# HDMI_Extension_Schematics.net
KiCad netlist of a schematic drawn in Altium Designer
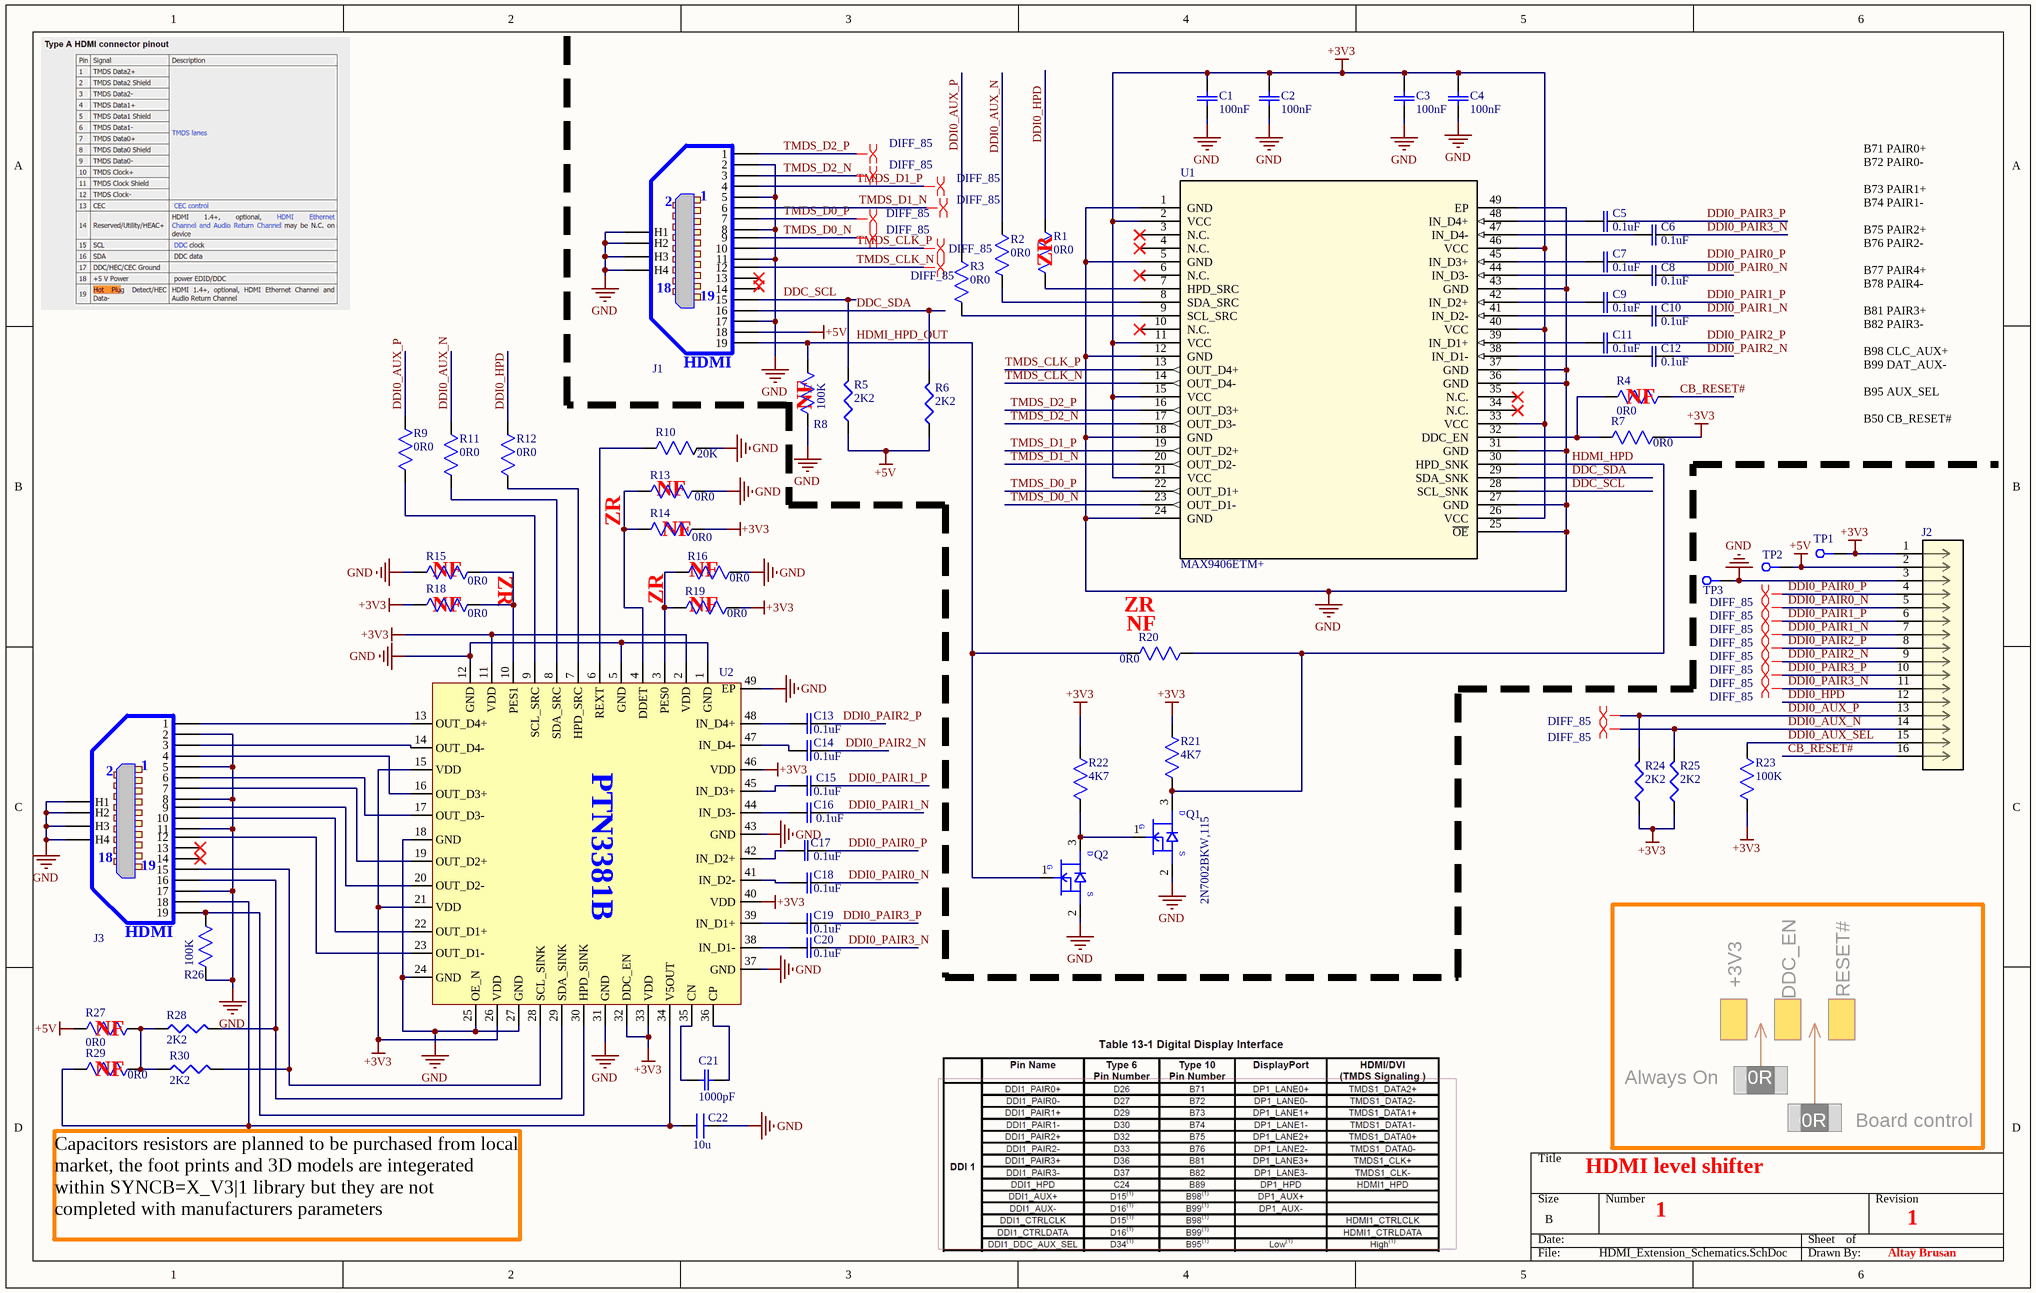
[diagram p0: HDMI_Extension_Schematics.SchDoc]

(export (version "E")
  (design (tool "Eeschema 10.0.6"))
  (components
    (comp (ref "C1")
      (value "100nF")
      (footprint "STA_RMCF1206-M")
      (description "CAP CER 0.1UF 50V X8R 0603")
      (fields (field (name "TOLERANCE") "±10%"))
      (libsource (lib "SYNCBOX_V3I1") (part "CL05A104KA5NNNC"))
    )
    (comp (ref "C2")
      (value "100nF")
      (footprint "STA_RMCF1206-M")
      (description "CAP CER 0.1UF 50V X8R 0603")
      (fields (field (name "TOLERANCE") "±10%"))
      (libsource (lib "SYNCBOX_V3I1") (part "CL05A104KA5NNNC"))
    )
    (comp (ref "C3")
      (value "100nF")
      (footprint "STA_RMCF1206-M")
      (description "CAP CER 0.1UF 50V X8R 0603")
      (fields (field (name "TOLERANCE") "±10%"))
      (libsource (lib "SYNCBOX_V3I1") (part "CL05A104KA5NNNC"))
    )
    (comp (ref "C4")
      (value "100nF")
      (footprint "STA_RMCF1206-M")
      (description "CAP CER 0.1UF 50V X8R 0603")
      (fields (field (name "TOLERANCE") "±10%"))
      (libsource (lib "SYNCBOX_V3I1") (part "CL05A104KA5NNNC"))
    )
    (comp (ref "C5")
      (value "0.1uF")
      (footprint "CAP_3216")
      (description "CAP CER 0.1UF 100V X8R 1206")
      (fields
        (field (name "MANUFACTURER_PART_NUMBER") "C3216X8R2A104K115AA")
        (field (name "COPYRIGHT") "Copyright (C) 2018 Accelerated Designs. All rights reserved")
      )
      (libsource (lib "SYNCBOX_V3I1") (part "C3216X8R2A104K11"))
    )
    (comp (ref "C6")
      (value "0.1uF")
      (footprint "CAP_3216")
      (description "CAP CER 0.1UF 100V X8R 1206")
      (fields
        (field (name "MANUFACTURER_PART_NUMBER") "C3216X8R2A104K115AA")
        (field (name "COPYRIGHT") "Copyright (C) 2018 Accelerated Designs. All rights reserved")
      )
      (libsource (lib "SYNCBOX_V3I1") (part "C3216X8R2A104K11"))
    )
    (comp (ref "C7")
      (value "0.1uF")
      (footprint "CAP_3216")
      (description "CAP CER 0.1UF 100V X8R 1206")
      (fields
        (field (name "MANUFACTURER_PART_NUMBER") "C3216X8R2A104K115AA")
        (field (name "COPYRIGHT") "Copyright (C) 2018 Accelerated Designs. All rights reserved")
      )
      (libsource (lib "SYNCBOX_V3I1") (part "C3216X8R2A104K11"))
    )
    (comp (ref "C8")
      (value "0.1uF")
      (footprint "CAP_3216")
      (description "CAP CER 0.1UF 100V X8R 1206")
      (fields
        (field (name "MANUFACTURER_PART_NUMBER") "C3216X8R2A104K115AA")
        (field (name "COPYRIGHT") "Copyright (C) 2018 Accelerated Designs. All rights reserved")
      )
      (libsource (lib "SYNCBOX_V3I1") (part "C3216X8R2A104K11"))
    )
    (comp (ref "C9")
      (value "0.1uF")
      (footprint "CAP_3216")
      (description "CAP CER 0.1UF 100V X8R 1206")
      (fields
        (field (name "MANUFACTURER_PART_NUMBER") "C3216X8R2A104K115AA")
        (field (name "COPYRIGHT") "Copyright (C) 2018 Accelerated Designs. All rights reserved")
      )
      (libsource (lib "SYNCBOX_V3I1") (part "C3216X8R2A104K11"))
    )
    (comp (ref "C10")
      (value "0.1uF")
      (footprint "CAP_3216")
      (description "CAP CER 0.1UF 100V X8R 1206")
      (fields
        (field (name "MANUFACTURER_PART_NUMBER") "C3216X8R2A104K115AA")
        (field (name "COPYRIGHT") "Copyright (C) 2018 Accelerated Designs. All rights reserved")
      )
      (libsource (lib "SYNCBOX_V3I1") (part "C3216X8R2A104K11"))
    )
    (comp (ref "C11")
      (value "0.1uF")
      (footprint "CAP_3216")
      (description "CAP CER 0.1UF 100V X8R 1206")
      (fields
        (field (name "MANUFACTURER_PART_NUMBER") "C3216X8R2A104K115AA")
        (field (name "COPYRIGHT") "Copyright (C) 2018 Accelerated Designs. All rights reserved")
      )
      (libsource (lib "SYNCBOX_V3I1") (part "C3216X8R2A104K11"))
    )
    (comp (ref "C12")
      (value "0.1uF")
      (footprint "CAP_3216")
      (description "CAP CER 0.1UF 100V X8R 1206")
      (fields
        (field (name "MANUFACTURER_PART_NUMBER") "C3216X8R2A104K115AA")
        (field (name "COPYRIGHT") "Copyright (C) 2018 Accelerated Designs. All rights reserved")
      )
      (libsource (lib "SYNCBOX_V3I1") (part "C3216X8R2A104K11"))
    )
    (comp (ref "C13")
      (value "0.1uF")
      (footprint "CAP_3216")
      (description "CAP CER 0.1UF 100V X8R 1206")
      (fields
        (field (name "MANUFACTURER_PART_NUMBER") "C3216X8R2A104K115AA")
        (field (name "COPYRIGHT") "Copyright (C) 2018 Accelerated Designs. All rights reserved")
      )
      (libsource (lib "SYNCBOX_V3I1") (part "C3216X8R2A104K11"))
    )
    (comp (ref "C14")
      (value "0.1uF")
      (footprint "CAP_3216")
      (description "CAP CER 0.1UF 100V X8R 1206")
      (fields
        (field (name "MANUFACTURER_PART_NUMBER") "C3216X8R2A104K115AA")
        (field (name "COPYRIGHT") "Copyright (C) 2018 Accelerated Designs. All rights reserved")
      )
      (libsource (lib "SYNCBOX_V3I1") (part "C3216X8R2A104K11"))
    )
    (comp (ref "C15")
      (value "0.1uF")
      (footprint "CAP_3216")
      (description "CAP CER 0.1UF 100V X8R 1206")
      (fields
        (field (name "MANUFACTURER_PART_NUMBER") "C3216X8R2A104K115AA")
        (field (name "COPYRIGHT") "Copyright (C) 2018 Accelerated Designs. All rights reserved")
      )
      (libsource (lib "SYNCBOX_V3I1") (part "C3216X8R2A104K11"))
    )
    (comp (ref "C16")
      (value "0.1uF")
      (footprint "CAP_3216")
      (description "CAP CER 0.1UF 100V X8R 1206")
      (fields
        (field (name "MANUFACTURER_PART_NUMBER") "C3216X8R2A104K115AA")
        (field (name "COPYRIGHT") "Copyright (C) 2018 Accelerated Designs. All rights reserved")
      )
      (libsource (lib "SYNCBOX_V3I1") (part "C3216X8R2A104K11"))
    )
    (comp (ref "C17")
      (value "0.1uF")
      (footprint "CAP_3216")
      (description "CAP CER 0.1UF 100V X8R 1206")
      (fields
        (field (name "MANUFACTURER_PART_NUMBER") "C3216X8R2A104K115AA")
        (field (name "COPYRIGHT") "Copyright (C) 2018 Accelerated Designs. All rights reserved")
      )
      (libsource (lib "SYNCBOX_V3I1") (part "C3216X8R2A104K11"))
    )
    (comp (ref "C18")
      (value "0.1uF")
      (footprint "CAP_3216")
      (description "CAP CER 0.1UF 100V X8R 1206")
      (fields
        (field (name "MANUFACTURER_PART_NUMBER") "C3216X8R2A104K115AA")
        (field (name "COPYRIGHT") "Copyright (C) 2018 Accelerated Designs. All rights reserved")
      )
      (libsource (lib "SYNCBOX_V3I1") (part "C3216X8R2A104K11"))
    )
    (comp (ref "C19")
      (value "0.1uF")
      (footprint "CAP_3216")
      (description "CAP CER 0.1UF 100V X8R 1206")
      (fields
        (field (name "MANUFACTURER_PART_NUMBER") "C3216X8R2A104K115AA")
        (field (name "COPYRIGHT") "Copyright (C) 2018 Accelerated Designs. All rights reserved")
      )
      (libsource (lib "SYNCBOX_V3I1") (part "C3216X8R2A104K11"))
    )
    (comp (ref "C20")
      (value "0.1uF")
      (footprint "CAP_3216")
      (description "CAP CER 0.1UF 100V X8R 1206")
      (fields
        (field (name "MANUFACTURER_PART_NUMBER") "C3216X8R2A104K115AA")
        (field (name "COPYRIGHT") "Copyright (C) 2018 Accelerated Designs. All rights reserved")
      )
      (libsource (lib "SYNCBOX_V3I1") (part "C3216X8R2A104K11"))
    )
    (comp (ref "C21")
      (value "1000pF")
      (footprint "C1206")
      (description "CAP CER 1206 1NF 2000V X7R 10% F")
      (fields (field (name "TOLERANCE") "±10%"))
      (libsource (lib "SYNCBOX_V3I1") (part "C1206X102KGRACAUTO"))
    )
    (comp (ref "C22")
      (value "10u")
      (footprint "C1206")
      (description "CAP CER 10UF 6.3V X5R 20% 0603")
      (fields (field (name "MANUFACTURER PART NUMBER") "C1608X5R0J106M") (field (name "TOLERANCE") "±20%"))
      (libsource (lib "SYNCBOX_V3I1") (part "C1608X5R0J106M"))
    )
    (comp (ref "J1")
      (value "HDMI Connector")
      (footprint "HDMI_Thru")
      (libsource (lib "SYNCBOX_V3I1") (part "HDMI_Connector"))
    )
    (comp (ref "J2")
      (value "Part Number: FTS-108-01-F-D")
      (footprint "CON16_2x8_TU_FTS")
      (description "No Description Available")
      (fields
        (field (name "MANUFACTURER_PART_NUMBER") "FTS-108-01-F-D")
        (field (name "COPYRIGHT") "Copyright (C) 2018 Accelerated Designs. All rights reserved")
      )
      (libsource (lib "SYNCBOX_V3I1") (part "FTS-108-01-F-D"))
    )
    (comp (ref "J3")
      (value "HDMI Connector")
      (footprint "HDMI_Thru")
      (libsource (lib "SYNCBOX_V3I1") (part "HDMI_Connector"))
    )
    (comp (ref "Q1")
      (value "2N7002BKW,115")
      (footprint "SC70_SOT323")
      (description "MOSFET N-CH 60V 310MA SOT323")
      (fields
        (field (name "MANUFACTURER") "NXP Semiconductors")
        (field (name ".CHECKED PCB") "RF")
        (field (name ".CHECKED SCH") "RF")
      )
      (libsource (lib "SYNCBOX_V3I1") (part "2N7002BKW,115"))
    )
    (comp (ref "Q2")
      (value "2N7002BKW,115")
      (footprint "SC70_SOT323")
      (description "MOSFET N-CH 60V 310MA SOT323")
      (fields
        (field (name "MANUFACTURER") "NXP Semiconductors")
        (field (name ".CHECKED PCB") "RF")
        (field (name ".CHECKED SCH") "RF")
      )
      (libsource (lib "SYNCBOX_V3I1") (part "2N7002BKW,115"))
    )
    (comp (ref "R1")
      (value "0R0")
      (footprint "STA_RMCF1206-M")
      (description "No Description Available")
      (fields
        (field (name "MANUFACTURER_PART_NUMBER") "RMCF1206JT390R")
        (field (name "TOLERANCE") "±5%")
        (field (name "COPYRIGHT") "Copyright (C) 2018 Accelerated Designs. All rights reserved")
      )
      (libsource (lib "SYNCBOX_V3I1") (part "RMCF1206JT390R"))
    )
    (comp (ref "R2")
      (value "0R0")
      (footprint "STA_RMCF1206-M")
      (description "No Description Available")
      (fields
        (field (name "MANUFACTURER_PART_NUMBER") "RMCF1206JT390R")
        (field (name "TOLERANCE") "±5%")
        (field (name "COPYRIGHT") "Copyright (C) 2018 Accelerated Designs. All rights reserved")
      )
      (libsource (lib "SYNCBOX_V3I1") (part "RMCF1206JT390R"))
    )
    (comp (ref "R3")
      (value "0R0")
      (footprint "STA_RMCF1206-M")
      (description "No Description Available")
      (fields
        (field (name "MANUFACTURER_PART_NUMBER") "RMCF1206JT390R")
        (field (name "TOLERANCE") "±5%")
        (field (name "COPYRIGHT") "Copyright (C) 2018 Accelerated Designs. All rights reserved")
      )
      (libsource (lib "SYNCBOX_V3I1") (part "RMCF1206JT390R"))
    )
    (comp (ref "R4")
      (value "0R0")
      (footprint "STA_RMCF1206-M")
      (description "No Description Available")
      (fields
        (field (name "MANUFACTURER_PART_NUMBER") "RMCF1206JT390R")
        (field (name "TOLERANCE") "±5%")
        (field (name "COPYRIGHT") "Copyright (C) 2018 Accelerated Designs. All rights reserved")
      )
      (libsource (lib "SYNCBOX_V3I1") (part "RMCF1206JT390R"))
    )
    (comp (ref "R5")
      (value "2K2")
      (footprint "R1210")
      (description "RES.(3225) 1210 2.2K Ohms 1% 1/3W-S 100PPM")
      (fields (field (name "TOLERANCE") "±1%"))
      (libsource (lib "SYNCBOX_V3I1") (part "RC1005F222CS"))
    )
    (comp (ref "R6")
      (value "2K2")
      (footprint "R1210")
      (description "RES.(3225) 1210 2.2K Ohms 1% 1/3W-S 100PPM")
      (fields (field (name "TOLERANCE") "±1%"))
      (libsource (lib "SYNCBOX_V3I1") (part "RC1005F222CS"))
    )
    (comp (ref "R7")
      (value "0R0")
      (footprint "STA_RMCF1206-M")
      (description "No Description Available")
      (fields
        (field (name "TOLERANCE") "±5%")
        (field (name "MANUFACTURER_PART_NUMBER") "RMCF1206JT390R")
        (field (name "COPYRIGHT") "Copyright (C) 2018 Accelerated Designs. All rights reserved")
      )
      (libsource (lib "SYNCBOX_V3I1") (part "RMCF1206JT390R"))
    )
    (comp (ref "R8")
      (value "100K")
      (footprint "STA_RMCF1206-M")
      (description "RES.(3216) 1206 100K Ohms 1% 1/4W-S 100PPM")
      (fields (field (name "TOLERANCE") "±1%"))
      (libsource (lib "SYNCBOX_V3I1") (part "RC2012F104CS"))
    )
    (comp (ref "R9")
      (value "0R0")
      (footprint "STA_RMCF1206-M")
      (description "No Description Available")
      (fields
        (field (name "MANUFACTURER_PART_NUMBER") "RMCF1206JT390R")
        (field (name "TOLERANCE") "±5%")
        (field (name "COPYRIGHT") "Copyright (C) 2018 Accelerated Designs. All rights reserved")
      )
      (libsource (lib "SYNCBOX_V3I1") (part "RMCF1206JT390R"))
    )
    (comp (ref "R10")
      (value "20K")
      (footprint "STA_RMCF1206-M")
      (description "RES.(3216) 1206 20K Ohms 1% 1/4W-S 100PPM")
      (fields (field (name "TOLERANCE") "±1%"))
      (libsource (lib "SYNCBOX_V3I1") (part "RC2012F203CS"))
    )
    (comp (ref "R11")
      (value "0R0")
      (footprint "STA_RMCF1206-M")
      (description "No Description Available")
      (fields
        (field (name "MANUFACTURER_PART_NUMBER") "RMCF1206JT390R")
        (field (name "TOLERANCE") "±5%")
        (field (name "COPYRIGHT") "Copyright (C) 2018 Accelerated Designs. All rights reserved")
      )
      (libsource (lib "SYNCBOX_V3I1") (part "RMCF1206JT390R"))
    )
    (comp (ref "R12")
      (value "0R0")
      (footprint "STA_RMCF1206-M")
      (description "No Description Available")
      (fields
        (field (name "MANUFACTURER_PART_NUMBER") "RMCF1206JT390R")
        (field (name "TOLERANCE") "±5%")
        (field (name "COPYRIGHT") "Copyright (C) 2018 Accelerated Designs. All rights reserved")
      )
      (libsource (lib "SYNCBOX_V3I1") (part "RMCF1206JT390R"))
    )
    (comp (ref "R13")
      (value "0R0")
      (footprint "STA_RMCF1206-M")
      (description "No Description Available")
      (fields
        (field (name "TOLERANCE") "±5%")
        (field (name "MANUFACTURER_PART_NUMBER") "RMCF1206JT390R")
        (field (name "COPYRIGHT") "Copyright (C) 2018 Accelerated Designs. All rights reserved")
      )
      (libsource (lib "SYNCBOX_V3I1") (part "RMCF1206JT390R"))
    )
    (comp (ref "R14")
      (value "0R0")
      (footprint "STA_RMCF1206-M")
      (description "No Description Available")
      (fields
        (field (name "TOLERANCE") "±5%")
        (field (name "MANUFACTURER_PART_NUMBER") "RMCF1206JT390R")
        (field (name "COPYRIGHT") "Copyright (C) 2018 Accelerated Designs. All rights reserved")
      )
      (libsource (lib "SYNCBOX_V3I1") (part "RMCF1206JT390R"))
    )
    (comp (ref "R15")
      (value "0R0")
      (footprint "STA_RMCF1206-M")
      (description "No Description Available")
      (fields
        (field (name "TOLERANCE") "±5%")
        (field (name "MANUFACTURER_PART_NUMBER") "RMCF1206JT390R")
        (field (name "COPYRIGHT") "Copyright (C) 2018 Accelerated Designs. All rights reserved")
      )
      (libsource (lib "SYNCBOX_V3I1") (part "RMCF1206JT390R"))
    )
    (comp (ref "R16")
      (value "0R0")
      (footprint "STA_RMCF1206-M")
      (description "No Description Available")
      (fields
        (field (name "TOLERANCE") "±5%")
        (field (name "MANUFACTURER_PART_NUMBER") "RMCF1206JT390R")
        (field (name "COPYRIGHT") "Copyright (C) 2018 Accelerated Designs. All rights reserved")
      )
      (libsource (lib "SYNCBOX_V3I1") (part "RMCF1206JT390R"))
    )
    (comp (ref "R18")
      (value "0R0")
      (footprint "STA_RMCF1206-M")
      (description "No Description Available")
      (fields
        (field (name "TOLERANCE") "±5%")
        (field (name "MANUFACTURER_PART_NUMBER") "RMCF1206JT390R")
        (field (name "COPYRIGHT") "Copyright (C) 2018 Accelerated Designs. All rights reserved")
      )
      (libsource (lib "SYNCBOX_V3I1") (part "RMCF1206JT390R"))
    )
    (comp (ref "R19")
      (value "0R0")
      (footprint "STA_RMCF1206-M")
      (description "No Description Available")
      (fields
        (field (name "TOLERANCE") "±5%")
        (field (name "MANUFACTURER_PART_NUMBER") "RMCF1206JT390R")
        (field (name "COPYRIGHT") "Copyright (C) 2018 Accelerated Designs. All rights reserved")
      )
      (libsource (lib "SYNCBOX_V3I1") (part "RMCF1206JT390R"))
    )
    (comp (ref "R20")
      (value "0R0")
      (footprint "STA_RMCF1206-M")
      (description "No Description Available")
      (fields
        (field (name "MANUFACTURER_PART_NUMBER") "RMCF1206JT390R")
        (field (name "TOLERANCE") "±5%")
        (field (name "COPYRIGHT") "Copyright (C) 2018 Accelerated Designs. All rights reserved")
      )
      (libsource (lib "SYNCBOX_V3I1") (part "RMCF1206JT390R"))
    )
    (comp (ref "R21")
      (value "4K7")
      (footprint "STA_RMCF1206-M")
      (description "RES SMD 4.7K OHM 1% 1/8W 0805")
      (fields (field (name "MANUFACTURER_PART_NUMBER") "CRG0805F4K7") (field (name "TOLERANCE") "±1%"))
      (libsource (lib "SYNCBOX_V3I1") (part "CRG0805F4K7"))
    )
    (comp (ref "R22")
      (value "4K7")
      (footprint "STA_RMCF1206-M")
      (description "RES SMD 4.7K OHM 1% 1/8W 0805")
      (fields (field (name "MANUFACTURER_PART_NUMBER") "CRG0805F4K7") (field (name "TOLERANCE") "±1%"))
      (libsource (lib "SYNCBOX_V3I1") (part "CRG0805F4K7"))
    )
    (comp (ref "R23")
      (value "100K")
      (footprint "STA_RMCF1206-M")
      (description "RES.(3216) 1206 100K Ohms 1% 1/4W-S 100PPM")
      (fields (field (name "TOLERANCE") "±1%"))
      (libsource (lib "SYNCBOX_V3I1") (part "RC2012F104CS"))
    )
    (comp (ref "R24")
      (value "2K2")
      (footprint "R1206")
      (description "RES.(3216) 1206 2.2K Ohms 1% 1/4W-S 100PPM")
      (fields (field (name "TOLERANCE") "±1%"))
      (libsource (lib "SYNCBOX_V3I1") (part "RC1005F222CS"))
    )
    (comp (ref "R25")
      (value "2K2")
      (footprint "R1206")
      (description "RES.(3216) 1206 2.2K Ohms 1% 1/4W-S 100PPM")
      (fields (field (name "TOLERANCE") "±1%"))
      (libsource (lib "SYNCBOX_V3I1") (part "RC1005F222CS"))
    )
    (comp (ref "R26")
      (value "100K")
      (footprint "STA_RMCF1206-M")
      (description "RES.(3216) 1206 100K Ohms 1% 1/4W-S 100PPM")
      (fields (field (name "TOLERANCE") "±1%"))
      (libsource (lib "SYNCBOX_V3I1") (part "RC2012F104CS"))
    )
    (comp (ref "R27")
      (value "0R0")
      (footprint "STA_RMCF1206-M")
      (description "No Description Available")
      (fields
        (field (name "TOLERANCE") "±5%")
        (field (name "MANUFACTURER_PART_NUMBER") "RMCF1206JT390R")
        (field (name "COPYRIGHT") "Copyright (C) 2018 Accelerated Designs. All rights reserved")
      )
      (libsource (lib "SYNCBOX_V3I1") (part "RMCF1206JT390R"))
    )
    (comp (ref "R28")
      (value "2K2")
      (footprint "R1206")
      (description "RES.(3216) 1206 2.2K Ohms 1% 1/4W-S 100PPM")
      (fields (field (name "TOLERANCE") "±1%"))
      (libsource (lib "SYNCBOX_V3I1") (part "RC1005F222CS"))
    )
    (comp (ref "R29")
      (value "0R0")
      (footprint "STA_RMCF1206-M")
      (description "No Description Available")
      (fields
        (field (name "TOLERANCE") "±5%")
        (field (name "MANUFACTURER_PART_NUMBER") "RMCF1206JT390R")
        (field (name "COPYRIGHT") "Copyright (C) 2018 Accelerated Designs. All rights reserved")
      )
      (libsource (lib "SYNCBOX_V3I1") (part "RMCF1206JT390R"))
    )
    (comp (ref "R30")
      (value "2K2")
      (footprint "R1206")
      (description "RES.(3216) 1206 2.2K Ohms 1% 1/4W-S 100PPM")
      (fields (field (name "TOLERANCE") "±1%"))
      (libsource (lib "SYNCBOX_V3I1") (part "RC1005F222CS"))
    )
    (comp (ref "TP1")
      (value "TP_25MILC")
      (footprint "TP_25C")
      (description "Test Point 25mil")
      (libsource (lib "SYNCBOX_V3I1") (part "TP_25MILC"))
    )
    (comp (ref "TP2")
      (value "TP_25MILC")
      (footprint "TP_25C")
      (description "Test Point 25mil")
      (libsource (lib "SYNCBOX_V3I1") (part "TP_25MILC"))
    )
    (comp (ref "TP3")
      (value "TP_25MILC")
      (footprint "TP_25C")
      (description "Test Point 25mil")
      (libsource (lib "SYNCBOX_V3I1") (part "TP_25MILC"))
    )
    (comp (ref "U1")
      (value "MAX9406ETM+")
      (footprint "21-0144H_T4877-6")
      (description "IC DVI/HDMI LVL SHIFTR 48TQFN")
      (fields (field (name "BASE PART NUMBER") "MAX9406"))
      (libsource (lib "SYNCBOX_V3I1") (part "MAX9406ETM+"))
    )
    (comp (ref "U2")
      (value "Interface - Specialized ENHNCD PERFORMANCE HDMI/DVI SHFTR V-REG")
      (footprint "HVQFN48")
      (libsource (lib "SYNCBOX_V3I1") (part "PTN3381B"))
    )
  )
  (nets
    (net (code "1") (name "+3V3") (class "Default")
      (node (ref "C1") (pin "2") (pinfunction "2_2") (pintype "passive"))
      (node (ref "C2") (pin "2") (pinfunction "2_2") (pintype "passive"))
      (node (ref "C3") (pin "2") (pinfunction "2_2") (pintype "passive"))
      (node (ref "C4") (pin "2") (pinfunction "2_2") (pintype "passive"))
      (node (ref "J2") (pin "1") (pinfunction "1_1") (pintype "passive"))
      (node (ref "R14") (pin "1") (pinfunction "1_1") (pintype "passive"))
      (node (ref "R18") (pin "2") (pinfunction "2_2") (pintype "passive"))
      (node (ref "R19") (pin "1") (pinfunction "1_1") (pintype "passive"))
      (node (ref "R21") (pin "1") (pinfunction "1_1") (pintype "passive"))
      (node (ref "R22") (pin "1") (pinfunction "1_1") (pintype "passive"))
      (node (ref "R23") (pin "2") (pinfunction "2_2") (pintype "passive"))
      (node (ref "R24") (pin "1") (pinfunction "1_1") (pintype "passive"))
      (node (ref "R25") (pin "1") (pinfunction "1_1") (pintype "passive"))
      (node (ref "R7") (pin "2") (pinfunction "2_2") (pintype "passive"))
      (node (ref "TP1") (pin "1") (pinfunction "1_1") (pintype "passive"))
      (node (ref "U1") (pin "11") (pinfunction "VCC_11") (pintype "power_in"))
      (node (ref "U1") (pin "15") (pinfunction "VCC_15") (pintype "power_in"))
      (node (ref "U1") (pin "2") (pinfunction "VCC_2") (pintype "power_in"))
      (node (ref "U1") (pin "21") (pinfunction "VCC_21") (pintype "passive"))
      (node (ref "U1") (pin "26") (pinfunction "VCC_26") (pintype "power_in"))
      (node (ref "U1") (pin "33") (pinfunction "VCC_33") (pintype "power_in"))
      (node (ref "U1") (pin "40") (pinfunction "VCC_40") (pintype "power_in"))
      (node (ref "U1") (pin "46") (pinfunction "VCC_46") (pintype "power_in"))
      (node (ref "U2") (pin "11") (pinfunction "VDD_11") (pintype "passive"))
      (node (ref "U2") (pin "15") (pinfunction "VDD_15") (pintype "passive"))
      (node (ref "U2") (pin "2") (pinfunction "VDD_2") (pintype "passive"))
      (node (ref "U2") (pin "21") (pinfunction "VDD_21") (pintype "passive"))
      (node (ref "U2") (pin "26") (pinfunction "VDD_26") (pintype "passive"))
      (node (ref "U2") (pin "32") (pinfunction "DDC_EN_32") (pintype "passive"))
      (node (ref "U2") (pin "33") (pinfunction "VDD_33") (pintype "passive"))
      (node (ref "U2") (pin "40") (pinfunction "VDD_40") (pintype "passive"))
      (node (ref "U2") (pin "46") (pinfunction "VDD_46") (pintype "passive"))
    )
    (net (code "2") (name "+5V") (class "Default")
      (node (ref "J1") (pin "18") (pinfunction "18_18") (pintype "passive"))
      (node (ref "J2") (pin "2") (pinfunction "2_2") (pintype "passive"))
      (node (ref "R27") (pin "2") (pinfunction "2_2") (pintype "passive"))
      (node (ref "R5") (pin "1") (pinfunction "1_1") (pintype "passive"))
      (node (ref "R6") (pin "1") (pinfunction "1_1") (pintype "passive"))
      (node (ref "TP2") (pin "1") (pinfunction "1_1") (pintype "passive"))
    )
    (net (code "3") (name "/CB_RESET#") (class "Default")
      (node (ref "J2") (pin "16") (pinfunction "16_16") (pintype "passive"))
      (node (ref "R4") (pin "2") (pinfunction "2_2") (pintype "passive"))
    )
    (net (code "4") (name "/DDC_SCL") (class "Default")
      (node (ref "J1") (pin "15") (pinfunction "15_15") (pintype "passive"))
      (node (ref "R5") (pin "2") (pinfunction "2_2") (pintype "passive"))
      (node (ref "U1") (pin "28") (pinfunction "SCL_SNK_28") (pintype "passive"))
    )
    (net (code "5") (name "/DDC_SDA") (class "Default")
      (node (ref "J1") (pin "16") (pinfunction "16_16") (pintype "passive"))
      (node (ref "R6") (pin "2") (pinfunction "2_2") (pintype "passive"))
      (node (ref "U1") (pin "29") (pinfunction "SDA_SNK_29") (pintype "passive"))
    )
    (net (code "6") (name "/DDI0_AUX_N") (class "Default")
      (node (ref "J2") (pin "14") (pinfunction "14_14") (pintype "passive"))
      (node (ref "R11") (pin "2") (pinfunction "2_2") (pintype "passive"))
      (node (ref "R2") (pin "2") (pinfunction "2_2") (pintype "passive"))
      (node (ref "R25") (pin "2") (pinfunction "2_2") (pintype "passive"))
    )
    (net (code "7") (name "/DDI0_AUX_P") (class "Default")
      (node (ref "J2") (pin "13") (pinfunction "13_13") (pintype "passive"))
      (node (ref "R24") (pin "2") (pinfunction "2_2") (pintype "passive"))
      (node (ref "R3") (pin "2") (pinfunction "2_2") (pintype "passive"))
      (node (ref "R9") (pin "2") (pinfunction "2_2") (pintype "passive"))
    )
    (net (code "8") (name "/DDI0_AUX_SEL") (class "Default")
      (node (ref "J2") (pin "15") (pinfunction "15_15") (pintype "passive"))
      (node (ref "R23") (pin "1") (pinfunction "1_1") (pintype "passive"))
    )
    (net (code "9") (name "/DDI0_HPD") (class "Default")
      (node (ref "J2") (pin "12") (pinfunction "12_12") (pintype "passive"))
      (node (ref "R1") (pin "2") (pinfunction "2_2") (pintype "passive"))
      (node (ref "R12") (pin "2") (pinfunction "2_2") (pintype "passive"))
    )
    (net (code "10") (name "/DDI0_PAIR0_N") (class "Default")
      (node (ref "C18") (pin "2") (pinfunction "2_2") (pintype "passive"))
      (node (ref "C8") (pin "2") (pinfunction "2_2") (pintype "passive"))
      (node (ref "J2") (pin "5") (pinfunction "5_5") (pintype "passive"))
    )
    (net (code "11") (name "/DDI0_PAIR0_P") (class "Default")
      (node (ref "C17") (pin "2") (pinfunction "2_2") (pintype "passive"))
      (node (ref "C7") (pin "2") (pinfunction "2_2") (pintype "passive"))
      (node (ref "J2") (pin "4") (pinfunction "4_4") (pintype "passive"))
    )
    (net (code "12") (name "/DDI0_PAIR1_N") (class "Default")
      (node (ref "C10") (pin "2") (pinfunction "2_2") (pintype "passive"))
      (node (ref "C16") (pin "2") (pinfunction "2_2") (pintype "passive"))
      (node (ref "J2") (pin "7") (pinfunction "7_7") (pintype "passive"))
    )
    (net (code "13") (name "/DDI0_PAIR1_P") (class "Default")
      (node (ref "C15") (pin "2") (pinfunction "2_2") (pintype "passive"))
      (node (ref "C9") (pin "2") (pinfunction "2_2") (pintype "passive"))
      (node (ref "J2") (pin "6") (pinfunction "6_6") (pintype "passive"))
    )
    (net (code "14") (name "/DDI0_PAIR2_N") (class "Default")
      (node (ref "C12") (pin "2") (pinfunction "2_2") (pintype "passive"))
      (node (ref "C14") (pin "2") (pinfunction "2_2") (pintype "passive"))
      (node (ref "J2") (pin "9") (pinfunction "9_9") (pintype "passive"))
    )
    (net (code "15") (name "/DDI0_PAIR2_P") (class "Default")
      (node (ref "C11") (pin "2") (pinfunction "2_2") (pintype "passive"))
      (node (ref "C13") (pin "2") (pinfunction "2_2") (pintype "passive"))
      (node (ref "J2") (pin "8") (pinfunction "8_8") (pintype "passive"))
    )
    (net (code "16") (name "/DDI0_PAIR3_N") (class "Default")
      (node (ref "C20") (pin "2") (pinfunction "2_2") (pintype "passive"))
      (node (ref "C6") (pin "2") (pinfunction "2_2") (pintype "passive"))
      (node (ref "J2") (pin "11") (pinfunction "11_11") (pintype "passive"))
    )
    (net (code "17") (name "/DDI0_PAIR3_P") (class "Default")
      (node (ref "C19") (pin "2") (pinfunction "2_2") (pintype "passive"))
      (node (ref "C5") (pin "2") (pinfunction "2_2") (pintype "passive"))
      (node (ref "J2") (pin "10") (pinfunction "10_10") (pintype "passive"))
    )
    (net (code "18") (name "/HDMI_HPD") (class "Default")
      (node (ref "Q1") (pin "3") (pinfunction "DRAIN_3") (pintype "passive"))
      (node (ref "R20") (pin "2") (pinfunction "2_2") (pintype "passive"))
      (node (ref "R21") (pin "2") (pinfunction "2_2") (pintype "passive"))
      (node (ref "U1") (pin "30") (pinfunction "HPD_SNK_30") (pintype "passive"))
    )
    (net (code "19") (name "/HDMI_HPD_OUT") (class "Default")
      (node (ref "J1") (pin "19") (pinfunction "19_19") (pintype "passive"))
      (node (ref "Q2") (pin "1") (pinfunction "GATE_1") (pintype "passive"))
      (node (ref "R20") (pin "1") (pinfunction "1_1") (pintype "passive"))
      (node (ref "R8") (pin "1") (pinfunction "1_1") (pintype "passive"))
    )
    (net (code "20") (name "/TMDS_CLK_N") (class "Default")
      (node (ref "J1") (pin "12") (pinfunction "12_12") (pintype "passive"))
      (node (ref "U1") (pin "14") (pinfunction "OUT_D4-_14") (pintype "output"))
    )
    (net (code "21") (name "/TMDS_CLK_P") (class "Default")
      (node (ref "J1") (pin "10") (pinfunction "10_10") (pintype "passive"))
      (node (ref "U1") (pin "13") (pinfunction "OUT_D4+_13") (pintype "output"))
    )
    (net (code "22") (name "/TMDS_D0_N") (class "Default")
      (node (ref "J1") (pin "9") (pinfunction "9_9") (pintype "passive"))
      (node (ref "U1") (pin "23") (pinfunction "OUT_D1-_23") (pintype "output"))
    )
    (net (code "23") (name "/TMDS_D0_P") (class "Default")
      (node (ref "J1") (pin "7") (pinfunction "7_7") (pintype "passive"))
      (node (ref "U1") (pin "22") (pinfunction "OUT_D1+_22") (pintype "output"))
    )
    (net (code "24") (name "/TMDS_D1_N") (class "Default")
      (node (ref "J1") (pin "6") (pinfunction "6_6") (pintype "passive"))
      (node (ref "U1") (pin "20") (pinfunction "OUT_D2-_20") (pintype "output"))
    )
    (net (code "25") (name "/TMDS_D1_P") (class "Default")
      (node (ref "J1") (pin "4") (pinfunction "4_4") (pintype "passive"))
      (node (ref "U1") (pin "19") (pinfunction "OUT_D2+_19") (pintype "output"))
    )
    (net (code "26") (name "/TMDS_D2_N") (class "Default")
      (node (ref "J1") (pin "3") (pinfunction "3_3") (pintype "passive"))
      (node (ref "U1") (pin "17") (pinfunction "OUT_D3-_17") (pintype "output"))
    )
    (net (code "27") (name "/TMDS_D2_P") (class "Default")
      (node (ref "J1") (pin "1") (pinfunction "1_1") (pintype "passive"))
      (node (ref "U1") (pin "16") (pinfunction "OUT_D3+_16") (pintype "output"))
    )
    (net (code "28") (name "GND") (class "Default")
      (node (ref "C1") (pin "1") (pinfunction "1_1") (pintype "passive"))
      (node (ref "C2") (pin "1") (pinfunction "1_1") (pintype "passive"))
      (node (ref "C22") (pin "2") (pinfunction "2_2") (pintype "passive"))
      (node (ref "C3") (pin "1") (pinfunction "1_1") (pintype "passive"))
      (node (ref "C4") (pin "1") (pinfunction "1_1") (pintype "passive"))
      (node (ref "J1") (pin "11") (pinfunction "11_11") (pintype "passive"))
      (node (ref "J1") (pin "17") (pinfunction "17_17") (pintype "passive"))
      (node (ref "J1") (pin "2") (pinfunction "2_2") (pintype "passive"))
      (node (ref "J1") (pin "5") (pinfunction "5_5") (pintype "passive"))
      (node (ref "J1") (pin "8") (pinfunction "8_8") (pintype "passive"))
      (node (ref "J1") (pin "H1") (pinfunction "H1_H1") (pintype "passive"))
      (node (ref "J1") (pin "H2") (pinfunction "H2_H2") (pintype "passive"))
      (node (ref "J1") (pin "H3") (pinfunction "H3_H3") (pintype "passive"))
      (node (ref "J1") (pin "H4") (pinfunction "H4_H4") (pintype "passive"))
      (node (ref "J2") (pin "3") (pinfunction "3_3") (pintype "passive"))
      (node (ref "J3") (pin "11") (pinfunction "11_11") (pintype "passive"))
      (node (ref "J3") (pin "17") (pinfunction "17_17") (pintype "passive"))
      (node (ref "J3") (pin "2") (pinfunction "2_2") (pintype "passive"))
      (node (ref "J3") (pin "5") (pinfunction "5_5") (pintype "passive"))
      (node (ref "J3") (pin "8") (pinfunction "8_8") (pintype "passive"))
      (node (ref "J3") (pin "H1") (pinfunction "H1_H1") (pintype "passive"))
      (node (ref "J3") (pin "H2") (pinfunction "H2_H2") (pintype "passive"))
      (node (ref "J3") (pin "H3") (pinfunction "H3_H3") (pintype "passive"))
      (node (ref "J3") (pin "H4") (pinfunction "H4_H4") (pintype "passive"))
      (node (ref "Q1") (pin "2") (pinfunction "SOURCE_2") (pintype "passive"))
      (node (ref "Q2") (pin "2") (pinfunction "SOURCE_2") (pintype "passive"))
      (node (ref "R10") (pin "2") (pinfunction "2_2") (pintype "passive"))
      (node (ref "R13") (pin "1") (pinfunction "1_1") (pintype "passive"))
      (node (ref "R15") (pin "2") (pinfunction "2_2") (pintype "passive"))
      (node (ref "R16") (pin "1") (pinfunction "1_1") (pintype "passive"))
      (node (ref "R26") (pin "2") (pinfunction "2_2") (pintype "passive"))
      (node (ref "R8") (pin "2") (pinfunction "2_2") (pintype "passive"))
      (node (ref "TP3") (pin "1") (pinfunction "1_1") (pintype "passive"))
      (node (ref "U1") (pin "1") (pinfunction "GND_1") (pintype "power_in"))
      (node (ref "U1") (pin "12") (pinfunction "GND_12") (pintype "power_in"))
      (node (ref "U1") (pin "18") (pinfunction "GND_18") (pintype "power_in"))
      (node (ref "U1") (pin "24") (pinfunction "GND_24") (pintype "power_in"))
      (node (ref "U1") (pin "25") (pinfunction "~{OE}_25") (pintype "passive"))
      (node (ref "U1") (pin "27") (pinfunction "GND_27") (pintype "power_in"))
      (node (ref "U1") (pin "31") (pinfunction "GND_31") (pintype "power_in"))
      (node (ref "U1") (pin "36") (pinfunction "GND_36") (pintype "power_in"))
      (node (ref "U1") (pin "37") (pinfunction "GND_37") (pintype "power_in"))
      (node (ref "U1") (pin "43") (pinfunction "GND_43") (pintype "power_in"))
      (node (ref "U1") (pin "49") (pinfunction "EP_49") (pintype "passive"))
      (node (ref "U1") (pin "5") (pinfunction "GND_5") (pintype "power_in"))
      (node (ref "U2") (pin "1") (pinfunction "GND_1") (pintype "passive"))
      (node (ref "U2") (pin "12") (pinfunction "GND_12") (pintype "passive"))
      (node (ref "U2") (pin "18") (pinfunction "GND_18") (pintype "passive"))
      (node (ref "U2") (pin "24") (pinfunction "GND_24") (pintype "passive"))
      (node (ref "U2") (pin "25") (pinfunction "OE_N_25") (pintype "passive"))
      (node (ref "U2") (pin "27") (pinfunction "GND_27") (pintype "passive"))
      (node (ref "U2") (pin "31") (pinfunction "GND_31") (pintype "passive"))
      (node (ref "U2") (pin "37") (pinfunction "GND_37") (pintype "passive"))
      (node (ref "U2") (pin "43") (pinfunction "GND_43") (pintype "passive"))
      (node (ref "U2") (pin "49") (pinfunction "EP_49") (pintype "passive"))
      (node (ref "U2") (pin "5") (pinfunction "GND_5") (pintype "passive"))
    )
    (net (code "29") (name "Net-(Q1-GATE)") (class "Default")
      (node (ref "Q1") (pin "1") (pinfunction "GATE_1") (pintype "passive"))
      (node (ref "Q2") (pin "3") (pinfunction "DRAIN_3") (pintype "passive"))
      (node (ref "R22") (pin "2") (pinfunction "2_2") (pintype "passive"))
    )
    (net (code "30") (name "Net-(R27-Pad1)") (class "Default")
      (node (ref "R27") (pin "1") (pinfunction "1_1") (pintype "passive"))
      (node (ref "R28") (pin "1") (pinfunction "1_1") (pintype "passive"))
      (node (ref "R29") (pin "2") (pinfunction "2_2") (pintype "passive"))
      (node (ref "R30") (pin "1") (pinfunction "1_1") (pintype "passive"))
    )
    (net (code "31") (name "Net-(U1-DDC_EN)") (class "Default")
      (node (ref "R4") (pin "1") (pinfunction "1_1") (pintype "passive"))
      (node (ref "R7") (pin "1") (pinfunction "1_1") (pintype "passive"))
      (node (ref "U1") (pin "32") (pinfunction "DDC_EN_32") (pintype "passive"))
    )
    (net (code "32") (name "Net-(U1-HPD_SRC)") (class "Default")
      (node (ref "R1") (pin "1") (pinfunction "1_1") (pintype "passive"))
      (node (ref "U1") (pin "7") (pinfunction "HPD_SRC_7") (pintype "passive"))
    )
    (net (code "33") (name "Net-(U1-IN_D1+)") (class "Default")
      (node (ref "C11") (pin "1") (pinfunction "1_1") (pintype "passive"))
      (node (ref "U1") (pin "39") (pinfunction "IN_D1+_39") (pintype "input"))
    )
    (net (code "34") (name "Net-(U1-IN_D1-)") (class "Default")
      (node (ref "C12") (pin "1") (pinfunction "1_1") (pintype "passive"))
      (node (ref "U1") (pin "38") (pinfunction "IN_D1-_38") (pintype "input"))
    )
    (net (code "35") (name "Net-(U1-IN_D2+)") (class "Default")
      (node (ref "C9") (pin "1") (pinfunction "1_1") (pintype "passive"))
      (node (ref "U1") (pin "42") (pinfunction "IN_D2+_42") (pintype "input"))
    )
    (net (code "36") (name "Net-(U1-IN_D2-)") (class "Default")
      (node (ref "C10") (pin "1") (pinfunction "1_1") (pintype "passive"))
      (node (ref "U1") (pin "41") (pinfunction "IN_D2-_41") (pintype "input"))
    )
    (net (code "37") (name "Net-(U1-IN_D3+)") (class "Default")
      (node (ref "C7") (pin "1") (pinfunction "1_1") (pintype "passive"))
      (node (ref "U1") (pin "45") (pinfunction "IN_D3+_45") (pintype "input"))
    )
    (net (code "38") (name "Net-(U1-IN_D3-)") (class "Default")
      (node (ref "C8") (pin "1") (pinfunction "1_1") (pintype "passive"))
      (node (ref "U1") (pin "44") (pinfunction "IN_D3-_44") (pintype "input"))
    )
    (net (code "39") (name "Net-(U1-IN_D4+)") (class "Default")
      (node (ref "C5") (pin "1") (pinfunction "1_1") (pintype "passive"))
      (node (ref "U1") (pin "48") (pinfunction "IN_D4+_48") (pintype "input"))
    )
    (net (code "40") (name "Net-(U1-IN_D4-)") (class "Default")
      (node (ref "C6") (pin "1") (pinfunction "1_1") (pintype "passive"))
      (node (ref "U1") (pin "47") (pinfunction "IN_D4-_47") (pintype "input"))
    )
    (net (code "41") (name "Net-(U1-SCL_SRC)") (class "Default")
      (node (ref "R3") (pin "1") (pinfunction "1_1") (pintype "passive"))
      (node (ref "U1") (pin "9") (pinfunction "SCL_SRC_9") (pintype "passive"))
    )
    (net (code "42") (name "Net-(U1-SDA_SRC)") (class "Default")
      (node (ref "R2") (pin "1") (pinfunction "1_1") (pintype "passive"))
      (node (ref "U1") (pin "8") (pinfunction "SDA_SRC_8") (pintype "passive"))
    )
    (net (code "43") (name "Net-(U2-CN)") (class "Default")
      (node (ref "C21") (pin "2") (pinfunction "2_2") (pintype "passive"))
      (node (ref "U2") (pin "35") (pinfunction "CN_35") (pintype "passive"))
    )
    (net (code "44") (name "Net-(U2-CP)") (class "Default")
      (node (ref "C21") (pin "1") (pinfunction "1_1") (pintype "passive"))
      (node (ref "U2") (pin "36") (pinfunction "CP_36") (pintype "passive"))
    )
    (net (code "45") (name "Net-(U2-DDET)") (class "Default")
      (node (ref "R13") (pin "2") (pinfunction "2_2") (pintype "passive"))
      (node (ref "R14") (pin "2") (pinfunction "2_2") (pintype "passive"))
      (node (ref "U2") (pin "4") (pinfunction "DDET_4") (pintype "passive"))
    )
    (net (code "46") (name "Net-(U2-HPD_SINK)") (class "Default")
      (node (ref "J3") (pin "19") (pinfunction "19_19") (pintype "passive"))
      (node (ref "R26") (pin "1") (pinfunction "1_1") (pintype "passive"))
      (node (ref "U2") (pin "30") (pinfunction "HPD_SINK_30") (pintype "passive"))
    )
    (net (code "47") (name "Net-(U2-HPD_SRC)") (class "Default")
      (node (ref "R12") (pin "1") (pinfunction "1_1") (pintype "passive"))
      (node (ref "U2") (pin "7") (pinfunction "HPD_SRC_7") (pintype "passive"))
    )
    (net (code "48") (name "Net-(U2-IN_D1+)") (class "Default")
      (node (ref "C19") (pin "1") (pinfunction "1_1") (pintype "passive"))
      (node (ref "U2") (pin "39") (pinfunction "IN_D1+_39") (pintype "passive"))
    )
    (net (code "49") (name "Net-(U2-IN_D1-)") (class "Default")
      (node (ref "C20") (pin "1") (pinfunction "1_1") (pintype "passive"))
      (node (ref "U2") (pin "38") (pinfunction "IN_D1-_38") (pintype "passive"))
    )
    (net (code "50") (name "Net-(U2-IN_D2+)") (class "Default")
      (node (ref "C17") (pin "1") (pinfunction "1_1") (pintype "passive"))
      (node (ref "U2") (pin "42") (pinfunction "IN_D2+_42") (pintype "passive"))
    )
    (net (code "51") (name "Net-(U2-IN_D2-)") (class "Default")
      (node (ref "C18") (pin "1") (pinfunction "1_1") (pintype "passive"))
      (node (ref "U2") (pin "41") (pinfunction "IN_D2-_41") (pintype "passive"))
    )
    (net (code "52") (name "Net-(U2-IN_D3+)") (class "Default")
      (node (ref "C15") (pin "1") (pinfunction "1_1") (pintype "passive"))
      (node (ref "U2") (pin "45") (pinfunction "IN_D3+_45") (pintype "passive"))
    )
    (net (code "53") (name "Net-(U2-IN_D3-)") (class "Default")
      (node (ref "C16") (pin "1") (pinfunction "1_1") (pintype "passive"))
      (node (ref "U2") (pin "44") (pinfunction "IN_D3-_44") (pintype "passive"))
    )
    (net (code "54") (name "Net-(U2-IN_D4+)") (class "Default")
      (node (ref "C13") (pin "1") (pinfunction "1_1") (pintype "passive"))
      (node (ref "U2") (pin "48") (pinfunction "IN_D4+_48") (pintype "passive"))
    )
    (net (code "55") (name "Net-(U2-IN_D4-)") (class "Default")
      (node (ref "C14") (pin "1") (pinfunction "1_1") (pintype "passive"))
      (node (ref "U2") (pin "47") (pinfunction "IN_D4-_47") (pintype "passive"))
    )
    (net (code "56") (name "Net-(U2-OUT_D1+)") (class "Default")
      (node (ref "J3") (pin "10") (pinfunction "10_10") (pintype "passive"))
      (node (ref "U2") (pin "22") (pinfunction "OUT_D1+_22") (pintype "passive"))
    )
    (net (code "57") (name "Net-(U2-OUT_D1-)") (class "Default")
      (node (ref "J3") (pin "12") (pinfunction "12_12") (pintype "passive"))
      (node (ref "U2") (pin "23") (pinfunction "OUT_D1-_23") (pintype "passive"))
    )
    (net (code "58") (name "Net-(U2-OUT_D2+)") (class "Default")
      (node (ref "J3") (pin "7") (pinfunction "7_7") (pintype "passive"))
      (node (ref "U2") (pin "19") (pinfunction "OUT_D2+_19") (pintype "passive"))
    )
    (net (code "59") (name "Net-(U2-OUT_D2-)") (class "Default")
      (node (ref "J3") (pin "9") (pinfunction "9_9") (pintype "passive"))
      (node (ref "U2") (pin "20") (pinfunction "OUT_D2-_20") (pintype "passive"))
    )
    (net (code "60") (name "Net-(U2-OUT_D3+)") (class "Default")
      (node (ref "J3") (pin "4") (pinfunction "4_4") (pintype "passive"))
      (node (ref "U2") (pin "16") (pinfunction "OUT_D3+_16") (pintype "passive"))
    )
    (net (code "61") (name "Net-(U2-OUT_D3-)") (class "Default")
      (node (ref "J3") (pin "6") (pinfunction "6_6") (pintype "passive"))
      (node (ref "U2") (pin "17") (pinfunction "OUT_D3-_17") (pintype "passive"))
    )
    (net (code "62") (name "Net-(U2-OUT_D4+)") (class "Default")
      (node (ref "J3") (pin "1") (pinfunction "1_1") (pintype "passive"))
      (node (ref "U2") (pin "13") (pinfunction "OUT_D4+_13") (pintype "passive"))
    )
    (net (code "63") (name "Net-(U2-OUT_D4-)") (class "Default")
      (node (ref "J3") (pin "3") (pinfunction "3_3") (pintype "passive"))
      (node (ref "U2") (pin "14") (pinfunction "OUT_D4-_14") (pintype "passive"))
    )
    (net (code "64") (name "Net-(U2-PES0)") (class "Default")
      (node (ref "R16") (pin "2") (pinfunction "2_2") (pintype "passive"))
      (node (ref "R19") (pin "2") (pinfunction "2_2") (pintype "passive"))
      (node (ref "U2") (pin "3") (pinfunction "PES0_3") (pintype "passive"))
    )
    (net (code "65") (name "Net-(U2-PES1)") (class "Default")
      (node (ref "R15") (pin "1") (pinfunction "1_1") (pintype "passive"))
      (node (ref "R18") (pin "1") (pinfunction "1_1") (pintype "passive"))
      (node (ref "U2") (pin "10") (pinfunction "PES1_10") (pintype "passive"))
    )
    (net (code "66") (name "Net-(U2-REXT)") (class "Default")
      (node (ref "R10") (pin "1") (pinfunction "1_1") (pintype "passive"))
      (node (ref "U2") (pin "6") (pinfunction "REXT_6") (pintype "passive"))
    )
    (net (code "67") (name "Net-(U2-SCL_SINK)") (class "Default")
      (node (ref "J3") (pin "15") (pinfunction "15_15") (pintype "passive"))
      (node (ref "R30") (pin "2") (pinfunction "2_2") (pintype "passive"))
      (node (ref "U2") (pin "28") (pinfunction "SCL_SINK_28") (pintype "passive"))
    )
    (net (code "68") (name "Net-(U2-SCL_SRC)") (class "Default")
      (node (ref "R9") (pin "1") (pinfunction "1_1") (pintype "passive"))
      (node (ref "U2") (pin "9") (pinfunction "SCL_SRC_9") (pintype "passive"))
    )
    (net (code "69") (name "Net-(U2-SDA_SINK)") (class "Default")
      (node (ref "J3") (pin "16") (pinfunction "16_16") (pintype "passive"))
      (node (ref "R28") (pin "2") (pinfunction "2_2") (pintype "passive"))
      (node (ref "U2") (pin "29") (pinfunction "SDA_SINK_29") (pintype "passive"))
    )
    (net (code "70") (name "Net-(U2-SDA_SRC)") (class "Default")
      (node (ref "R11") (pin "1") (pinfunction "1_1") (pintype "passive"))
      (node (ref "U2") (pin "8") (pinfunction "SDA_SRC_8") (pintype "passive"))
    )
    (net (code "71") (name "Net-(U2-V5OUT)") (class "Default")
      (node (ref "C22") (pin "1") (pinfunction "1_1") (pintype "passive"))
      (node (ref "J3") (pin "18") (pinfunction "18_18") (pintype "passive"))
      (node (ref "R29") (pin "1") (pinfunction "1_1") (pintype "passive"))
      (node (ref "U2") (pin "34") (pinfunction "V5OUT_34") (pintype "passive"))
    )
    (net (code "72") (name "unconnected-(J1-Pad13)") (class "Default")
      (node (ref "J1") (pin "13") (pinfunction "13_13") (pintype "passive+no_connect"))
    )
    (net (code "73") (name "unconnected-(J1-Pad14)") (class "Default")
      (node (ref "J1") (pin "14") (pinfunction "14_14") (pintype "passive"))
    )
    (net (code "74") (name "unconnected-(J3-Pad13)") (class "Default")
      (node (ref "J3") (pin "13") (pinfunction "13_13") (pintype "passive+no_connect"))
    )
    (net (code "75") (name "unconnected-(J3-Pad14)") (class "Default")
      (node (ref "J3") (pin "14") (pinfunction "14_14") (pintype "passive+no_connect"))
    )
    (net (code "76") (name "unconnected-(U1-N.C.-Pad3)") (class "Default")
      (node (ref "U1") (pin "3") (pinfunction "N.C._3") (pintype "passive+no_connect"))
    )
    (net (code "77") (name "unconnected-(U1-N.C.-Pad4)") (class "Default")
      (node (ref "U1") (pin "4") (pinfunction "N.C._4") (pintype "passive+no_connect"))
    )
    (net (code "78") (name "unconnected-(U1-N.C.-Pad6)") (class "Default")
      (node (ref "U1") (pin "6") (pinfunction "N.C._6") (pintype "passive+no_connect"))
    )
    (net (code "79") (name "unconnected-(U1-N.C.-Pad10)") (class "Default")
      (node (ref "U1") (pin "10") (pinfunction "N.C._10") (pintype "passive+no_connect"))
    )
    (net (code "80") (name "unconnected-(U1-N.C.-Pad34)") (class "Default")
      (node (ref "U1") (pin "34") (pinfunction "N.C._34") (pintype "passive+no_connect"))
    )
    (net (code "81") (name "unconnected-(U1-N.C.-Pad35)") (class "Default")
      (node (ref "U1") (pin "35") (pinfunction "N.C._35") (pintype "passive+no_connect"))
    )
  )
)
